# IMUCubeSL_Sch.net
KiCad netlist of a schematic drawn in Altium Designer
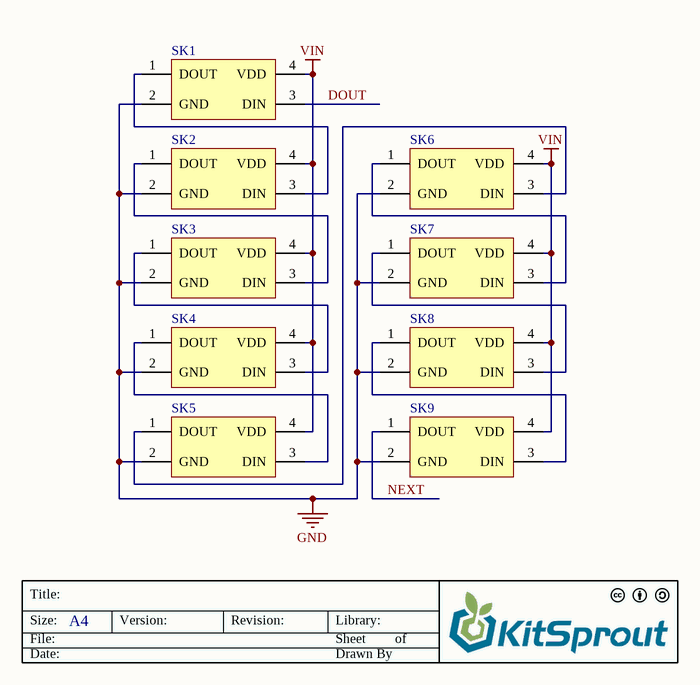
[diagram p0: IMUCubeSL_Sch.SchDoc]

(export (version "E")
  (design (tool "Eeschema 10.0.6"))
  (components
    (comp (ref "SK1")
      (value "LED_3535_SK6812")
      (footprint "PCB_ActiveLED:LED_3535_4P")
      (description "LED")
      (libsource (lib "SCH_Active") (part "LED_3535_SK6812"))
    )
    (comp (ref "SK2")
      (value "LED_3535_SK6812")
      (footprint "PCB_ActiveLED:LED_3535_4P")
      (description "LED")
      (libsource (lib "SCH_Active") (part "LED_3535_SK6812"))
    )
    (comp (ref "SK3")
      (value "LED_3535_SK6812")
      (footprint "PCB_ActiveLED:LED_3535_4P")
      (description "LED")
      (libsource (lib "SCH_Active") (part "LED_3535_SK6812"))
    )
    (comp (ref "SK4")
      (value "LED_3535_SK6812")
      (footprint "PCB_ActiveLED:LED_3535_4P")
      (description "LED")
      (libsource (lib "SCH_Active") (part "LED_3535_SK6812"))
    )
    (comp (ref "SK5")
      (value "LED_3535_SK6812")
      (footprint "PCB_ActiveLED:LED_3535_4P")
      (description "LED")
      (libsource (lib "SCH_Active") (part "LED_3535_SK6812"))
    )
    (comp (ref "SK6")
      (value "LED_3535_SK6812")
      (footprint "PCB_ActiveLED:LED_3535_4P")
      (description "LED")
      (libsource (lib "SCH_Active") (part "LED_3535_SK6812"))
    )
    (comp (ref "SK7")
      (value "LED_3535_SK6812")
      (footprint "PCB_ActiveLED:LED_3535_4P")
      (description "LED")
      (libsource (lib "SCH_Active") (part "LED_3535_SK6812"))
    )
    (comp (ref "SK8")
      (value "LED_3535_SK6812")
      (footprint "PCB_ActiveLED:LED_3535_4P")
      (description "LED")
      (libsource (lib "SCH_Active") (part "LED_3535_SK6812"))
    )
    (comp (ref "SK9")
      (value "LED_3535_SK6812")
      (footprint "PCB_ActiveLED:LED_3535_4P")
      (description "LED")
      (libsource (lib "SCH_Active") (part "LED_3535_SK6812"))
    )
  )
  (nets
    (net (code "1") (name "/DOUT") (class "Default")
      (node (ref "SK1") (pin "3") (pinfunction "DIN_3") (pintype "passive"))
    )
    (net (code "2") (name "/NEXT") (class "Default")
      (node (ref "SK9") (pin "1") (pinfunction "DOUT_1") (pintype "passive"))
    )
    (net (code "3") (name "GND") (class "Default")
      (node (ref "SK1") (pin "2") (pinfunction "GND_2") (pintype "passive"))
      (node (ref "SK2") (pin "2") (pinfunction "GND_2") (pintype "passive"))
      (node (ref "SK3") (pin "2") (pinfunction "GND_2") (pintype "passive"))
      (node (ref "SK4") (pin "2") (pinfunction "GND_2") (pintype "passive"))
      (node (ref "SK5") (pin "2") (pinfunction "GND_2") (pintype "passive"))
      (node (ref "SK6") (pin "2") (pinfunction "GND_2") (pintype "passive"))
      (node (ref "SK7") (pin "2") (pinfunction "GND_2") (pintype "passive"))
      (node (ref "SK8") (pin "2") (pinfunction "GND_2") (pintype "passive"))
      (node (ref "SK9") (pin "2") (pinfunction "GND_2") (pintype "passive"))
    )
    (net (code "4") (name "Net-(SK1-DOUT)") (class "Default")
      (node (ref "SK1") (pin "1") (pinfunction "DOUT_1") (pintype "passive"))
      (node (ref "SK2") (pin "3") (pinfunction "DIN_3") (pintype "passive"))
    )
    (net (code "5") (name "Net-(SK2-DOUT)") (class "Default")
      (node (ref "SK2") (pin "1") (pinfunction "DOUT_1") (pintype "passive"))
      (node (ref "SK3") (pin "3") (pinfunction "DIN_3") (pintype "passive"))
    )
    (net (code "6") (name "Net-(SK3-DOUT)") (class "Default")
      (node (ref "SK3") (pin "1") (pinfunction "DOUT_1") (pintype "passive"))
      (node (ref "SK4") (pin "3") (pinfunction "DIN_3") (pintype "passive"))
    )
    (net (code "7") (name "Net-(SK4-DOUT)") (class "Default")
      (node (ref "SK4") (pin "1") (pinfunction "DOUT_1") (pintype "passive"))
      (node (ref "SK5") (pin "3") (pinfunction "DIN_3") (pintype "passive"))
    )
    (net (code "8") (name "Net-(SK5-DOUT)") (class "Default")
      (node (ref "SK5") (pin "1") (pinfunction "DOUT_1") (pintype "passive"))
      (node (ref "SK6") (pin "3") (pinfunction "DIN_3") (pintype "passive"))
    )
    (net (code "9") (name "Net-(SK6-DOUT)") (class "Default")
      (node (ref "SK6") (pin "1") (pinfunction "DOUT_1") (pintype "passive"))
      (node (ref "SK7") (pin "3") (pinfunction "DIN_3") (pintype "passive"))
    )
    (net (code "10") (name "Net-(SK7-DOUT)") (class "Default")
      (node (ref "SK7") (pin "1") (pinfunction "DOUT_1") (pintype "passive"))
      (node (ref "SK8") (pin "3") (pinfunction "DIN_3") (pintype "passive"))
    )
    (net (code "11") (name "Net-(SK8-DOUT)") (class "Default")
      (node (ref "SK8") (pin "1") (pinfunction "DOUT_1") (pintype "passive"))
      (node (ref "SK9") (pin "3") (pinfunction "DIN_3") (pintype "passive"))
    )
    (net (code "12") (name "VIN") (class "Default")
      (node (ref "SK1") (pin "4") (pinfunction "VDD_4") (pintype "passive"))
      (node (ref "SK2") (pin "4") (pinfunction "VDD_4") (pintype "passive"))
      (node (ref "SK3") (pin "4") (pinfunction "VDD_4") (pintype "passive"))
      (node (ref "SK4") (pin "4") (pinfunction "VDD_4") (pintype "passive"))
      (node (ref "SK5") (pin "4") (pinfunction "VDD_4") (pintype "passive"))
      (node (ref "SK6") (pin "4") (pinfunction "VDD_4") (pintype "passive"))
      (node (ref "SK7") (pin "4") (pinfunction "VDD_4") (pintype "passive"))
      (node (ref "SK8") (pin "4") (pinfunction "VDD_4") (pintype "passive"))
      (node (ref "SK9") (pin "4") (pinfunction "VDD_4") (pintype "passive"))
    )
  )
)
